# AMS_Control.net
KiCad netlist of a schematic drawn in Altium Designer
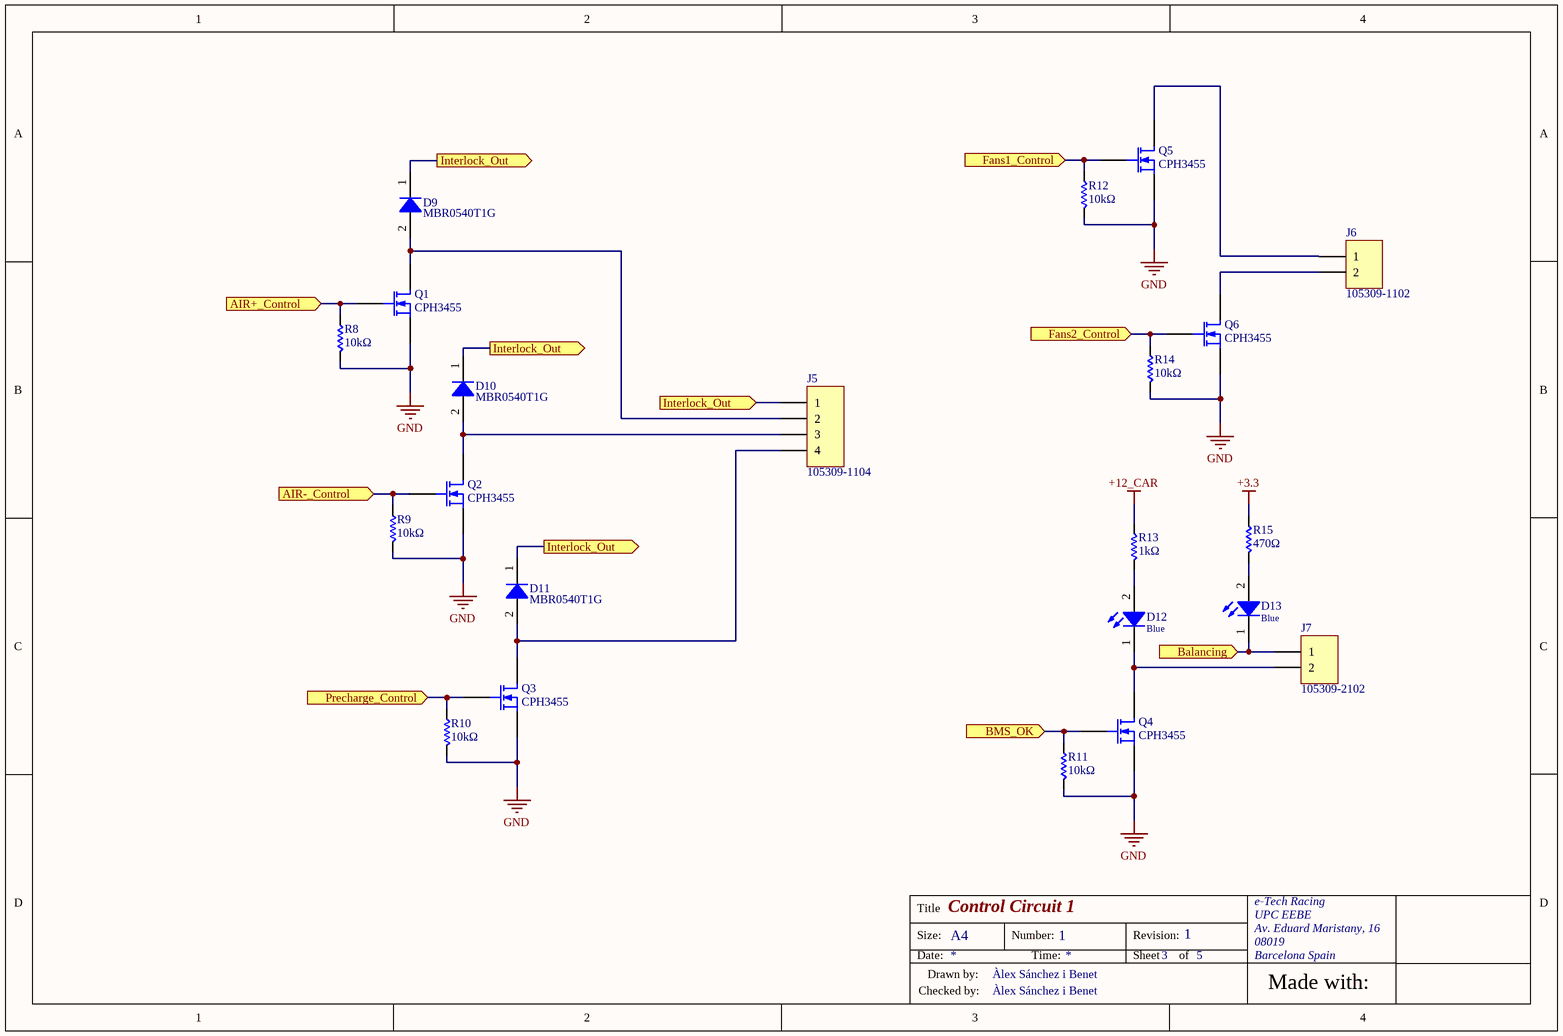
[diagram p0: AMS_Control.SchDoc]

(export (version "E")
  (design (tool "Eeschema 10.0.6"))
  (components
    (comp (ref "D9")
      (value "MBR0540T1G")
      (footprint "MBR0540T1G")
      (description "Surface Mount Schottky Power Rectifier")
      (fields (field (name "MANUFACTURER") "On Semiconductor"))
      (libsource (lib "Components_Library") (part "MBR0540T1G"))
    )
    (comp (ref "D10")
      (value "MBR0540T1G")
      (footprint "MBR0540T1G")
      (description "Surface Mount Schottky Power Rectifier")
      (fields (field (name "MANUFACTURER") "On Semiconductor"))
      (libsource (lib "Components_Library") (part "MBR0540T1G"))
    )
    (comp (ref "D11")
      (value "MBR0540T1G")
      (footprint "MBR0540T1G")
      (description "Surface Mount Schottky Power Rectifier")
      (fields (field (name "MANUFACTURER") "On Semiconductor"))
      (libsource (lib "Components_Library") (part "MBR0540T1G"))
    )
    (comp (ref "D12")
      (value "Blue")
      (footprint "WL-SMCW_0805")
      (description "SMT Mono-color Chip LED Waterclear WL-SMCW, size 0805, Blue, 3.2 V, 140 deg, 145 mcd")
      (fields (field (name "PART NUMBER") "150080BS75000") (field (name "PUBLISHER") "Wurth Elektronik"))
      (libsource (lib "TSAL_Control") (part "150080BS75000"))
    )
    (comp (ref "D13")
      (value "Blue")
      (footprint "WL-SMCW_0805")
      (description "SMT Mono-color Chip LED Waterclear WL-SMCW, size 0805, Blue, 3.2 V, 140 deg, 145 mcd")
      (fields (field (name "PART NUMBER") "150080BS75000") (field (name "PUBLISHER") "Wurth Elektronik"))
      (libsource (lib "Components_Library") (part "150080BS75000"))
    )
    (comp (ref "J5")
      (value "105309-1104")
      (footprint "105309-1104")
      (description "Nano-Fit Vertical Header, Through Hole, 2.50mm Pitch, Single Row, 4 Circuits, Black")
      (fields (field (name "MANUFACTURER") "Molex"))
      (libsource (lib "Components_Library") (part "105309-1104"))
    )
    (comp (ref "J6")
      (value "105309-1102")
      (footprint "105309-1102")
      (description "Nano-Fit Vertical Header, Through Hole, 2.50mm Pitch, Single Row, 2 Circuits, Black")
      (fields (field (name "MANUFACTURER") "Molex"))
      (libsource (lib "Components_Library") (part "105309-1102"))
    )
    (comp (ref "J7")
      (value "105309-2102")
      (footprint "105309-2102")
      (description "Nano-Fit Vertical Header, Through Hole, 2.50mm Pitch, Single Row, 2 Circuits, Natural")
      (fields (field (name "MANUFACTURER") "Molex"))
      (libsource (lib "Components_Library") (part "105309-2102"))
    )
    (comp (ref "Q1")
      (value "CPH3455")
      (footprint "CPH3455")
      (description "Power MOSFET 35V, 104mΩ, 3A, Single N-Channel")
      (fields (field (name "MANUFACTURER") "ON Semiconductors"))
      (libsource (lib "Components_Library") (part "CPH3455"))
    )
    (comp (ref "Q2")
      (value "CPH3455")
      (footprint "CPH3455")
      (description "Power MOSFET 35V, 104mΩ, 3A, Single N-Channel")
      (fields (field (name "MANUFACTURER") "ON Semiconductors"))
      (libsource (lib "Components_Library") (part "CPH3455"))
    )
    (comp (ref "Q3")
      (value "CPH3455")
      (footprint "CPH3455")
      (description "Power MOSFET 35V, 104mΩ, 3A, Single N-Channel")
      (fields (field (name "MANUFACTURER") "ON Semiconductors"))
      (libsource (lib "Components_Library") (part "CPH3455"))
    )
    (comp (ref "Q4")
      (value "CPH3455")
      (footprint "CPH3455")
      (description "Power MOSFET 35V, 104mΩ, 3A, Single N-Channel")
      (fields (field (name "MANUFACTURER") "ON Semiconductors"))
      (libsource (lib "Components_Library") (part "CPH3455"))
    )
    (comp (ref "Q5")
      (value "CPH3455")
      (footprint "CPH3455")
      (description "Power MOSFET 35V, 104mΩ, 3A, Single N-Channel")
      (fields (field (name "MANUFACTURER") "ON Semiconductors"))
      (libsource (lib "Components_Library") (part "CPH3455"))
    )
    (comp (ref "Q6")
      (value "CPH3455")
      (footprint "CPH3455")
      (description "Power MOSFET 35V, 104mΩ, 3A, Single N-Channel")
      (fields (field (name "MANUFACTURER") "ON Semiconductors"))
      (libsource (lib "Components_Library") (part "CPH3455"))
    )
    (comp (ref "R8")
      (value "10kΩ")
      (footprint "CR0805")
      (description "Chip Resistor 0805")
      (fields (field (name "MANUFACTURER") "Bourns"))
      (libsource (lib "Components_Library") (part "CR0805-JW-103ELF"))
    )
    (comp (ref "R9")
      (value "10kΩ")
      (footprint "CR0805")
      (description "Chip Resistor 0805")
      (fields (field (name "MANUFACTURER") "Bourns"))
      (libsource (lib "Components_Library") (part "CR0805-JW-103ELF"))
    )
    (comp (ref "R10")
      (value "10kΩ")
      (footprint "CR0805")
      (description "Chip Resistor 0805")
      (fields (field (name "MANUFACTURER") "Bourns"))
      (libsource (lib "Components_Library") (part "CR0805-JW-103ELF"))
    )
    (comp (ref "R11")
      (value "10kΩ")
      (footprint "CR0805")
      (description "Chip Resistor 0805")
      (fields (field (name "MANUFACTURER") "Bourns"))
      (libsource (lib "Components_Library") (part "CR0805-JW-103ELF"))
    )
    (comp (ref "R12")
      (value "10kΩ")
      (footprint "CR0805")
      (description "Chip Resistor 0805")
      (fields (field (name "MANUFACTURER") "Bourns"))
      (libsource (lib "Components_Library") (part "CR0805-JW-103ELF"))
    )
    (comp (ref "R13")
      (value "1kΩ")
      (footprint "CR0805")
      (description "Chip Resistor 0805")
      (fields (field (name "MANUFACTURER") "Bourns"))
      (libsource (lib "Components_Library") (part "CR0805-JW-103ELF"))
    )
    (comp (ref "R14")
      (value "10kΩ")
      (footprint "CR0805")
      (description "Chip Resistor 0805")
      (fields (field (name "MANUFACTURER") "Bourns"))
      (libsource (lib "Components_Library") (part "CR0805-JW-103ELF"))
    )
    (comp (ref "R15")
      (value "470Ω")
      (footprint "CR0805")
      (description "Chip Resistor 0805")
      (fields (field (name "MANUFACTURER") "Bourns"))
      (libsource (lib "Components_Library") (part "CR0805-FX-4700GLF"))
    )
  )
  (nets
    (net (code "1") (name "+3.3") (class "Default")
      (node (ref "R15") (pin "2") (pinfunction "2_2") (pintype "passive"))
    )
    (net (code "2") (name "+12_CAR") (class "Default")
      (node (ref "R13") (pin "2") (pinfunction "2_2") (pintype "passive"))
    )
    (net (code "3") (name "/AIR+_Control") (class "Default")
      (node (ref "Q1") (pin "1") (pinfunction "G_1") (pintype "passive"))
      (node (ref "R8") (pin "2") (pinfunction "2_2") (pintype "passive"))
    )
    (net (code "4") (name "/AIR-_Control") (class "Default")
      (node (ref "Q2") (pin "1") (pinfunction "G_1") (pintype "passive"))
      (node (ref "R9") (pin "2") (pinfunction "2_2") (pintype "passive"))
    )
    (net (code "5") (name "/BMS_OK") (class "Default")
      (node (ref "Q4") (pin "1") (pinfunction "G_1") (pintype "passive"))
      (node (ref "R11") (pin "2") (pinfunction "2_2") (pintype "passive"))
    )
    (net (code "6") (name "/Balancing") (class "Default")
      (node (ref "D13") (pin "1") (pinfunction "K_1") (pintype "passive"))
      (node (ref "J7") (pin "1") (pinfunction "1_1") (pintype "passive"))
    )
    (net (code "7") (name "/Fans1_Control") (class "Default")
      (node (ref "Q5") (pin "1") (pinfunction "G_1") (pintype "passive"))
      (node (ref "R12") (pin "2") (pinfunction "2_2") (pintype "passive"))
    )
    (net (code "8") (name "/Fans2_Control") (class "Default")
      (node (ref "Q6") (pin "1") (pinfunction "G_1") (pintype "passive"))
      (node (ref "R14") (pin "2") (pinfunction "2_2") (pintype "passive"))
    )
    (net (code "9") (name "/Interlock_Out") (class "Default")
      (node (ref "D10") (pin "1") (pinfunction "K_1") (pintype "passive"))
      (node (ref "D11") (pin "1") (pinfunction "K_1") (pintype "passive"))
      (node (ref "D9") (pin "1") (pinfunction "K_1") (pintype "passive"))
      (node (ref "J5") (pin "1") (pinfunction "1_1") (pintype "passive"))
    )
    (net (code "10") (name "/Precharge_Control") (class "Default")
      (node (ref "Q3") (pin "1") (pinfunction "G_1") (pintype "passive"))
      (node (ref "R10") (pin "2") (pinfunction "2_2") (pintype "passive"))
    )
    (net (code "11") (name "GND") (class "Default")
      (node (ref "Q1") (pin "2") (pinfunction "S_2") (pintype "passive"))
      (node (ref "Q2") (pin "2") (pinfunction "S_2") (pintype "passive"))
      (node (ref "Q3") (pin "2") (pinfunction "S_2") (pintype "passive"))
      (node (ref "Q4") (pin "2") (pinfunction "S_2") (pintype "passive"))
      (node (ref "Q5") (pin "2") (pinfunction "S_2") (pintype "passive"))
      (node (ref "Q6") (pin "2") (pinfunction "S_2") (pintype "passive"))
      (node (ref "R10") (pin "1") (pinfunction "1_1") (pintype "passive"))
      (node (ref "R11") (pin "1") (pinfunction "1_1") (pintype "passive"))
      (node (ref "R12") (pin "1") (pinfunction "1_1") (pintype "passive"))
      (node (ref "R14") (pin "1") (pinfunction "1_1") (pintype "passive"))
      (node (ref "R8") (pin "1") (pinfunction "1_1") (pintype "passive"))
      (node (ref "R9") (pin "1") (pinfunction "1_1") (pintype "passive"))
    )
    (net (code "12") (name "Net-(D9-A)") (class "Default")
      (node (ref "D9") (pin "2") (pinfunction "A_2") (pintype "passive"))
      (node (ref "J5") (pin "2") (pinfunction "2_2") (pintype "passive"))
      (node (ref "Q1") (pin "3") (pinfunction "D_3") (pintype "passive"))
    )
    (net (code "13") (name "Net-(D10-A)") (class "Default")
      (node (ref "D10") (pin "2") (pinfunction "A_2") (pintype "passive"))
      (node (ref "J5") (pin "3") (pinfunction "3_3") (pintype "passive"))
      (node (ref "Q2") (pin "3") (pinfunction "D_3") (pintype "passive"))
    )
    (net (code "14") (name "Net-(D11-A)") (class "Default")
      (node (ref "D11") (pin "2") (pinfunction "A_2") (pintype "passive"))
      (node (ref "J5") (pin "4") (pinfunction "4_4") (pintype "passive"))
      (node (ref "Q3") (pin "3") (pinfunction "D_3") (pintype "passive"))
    )
    (net (code "15") (name "Net-(D12-A)") (class "Default")
      (node (ref "D12") (pin "2") (pinfunction "A_2") (pintype "passive"))
      (node (ref "R13") (pin "1") (pinfunction "1_1") (pintype "passive"))
    )
    (net (code "16") (name "Net-(D12-K)") (class "Default")
      (node (ref "D12") (pin "1") (pinfunction "K_1") (pintype "passive"))
      (node (ref "J7") (pin "2") (pinfunction "2_2") (pintype "passive"))
      (node (ref "Q4") (pin "3") (pinfunction "D_3") (pintype "passive"))
    )
    (net (code "17") (name "Net-(D13-A)") (class "Default")
      (node (ref "D13") (pin "2") (pinfunction "A_2") (pintype "passive"))
      (node (ref "R15") (pin "1") (pinfunction "1_1") (pintype "passive"))
    )
    (net (code "18") (name "Net-(Q5-D)") (class "Default")
      (node (ref "J6") (pin "1") (pinfunction "1_1") (pintype "passive"))
      (node (ref "Q5") (pin "3") (pinfunction "D_3") (pintype "passive"))
    )
    (net (code "19") (name "Net-(Q6-D)") (class "Default")
      (node (ref "J6") (pin "2") (pinfunction "2_2") (pintype "passive"))
      (node (ref "Q6") (pin "3") (pinfunction "D_3") (pintype "passive"))
    )
  )
)
